# Sheet2.net
KiCad netlist of a schematic drawn in Altium Designer
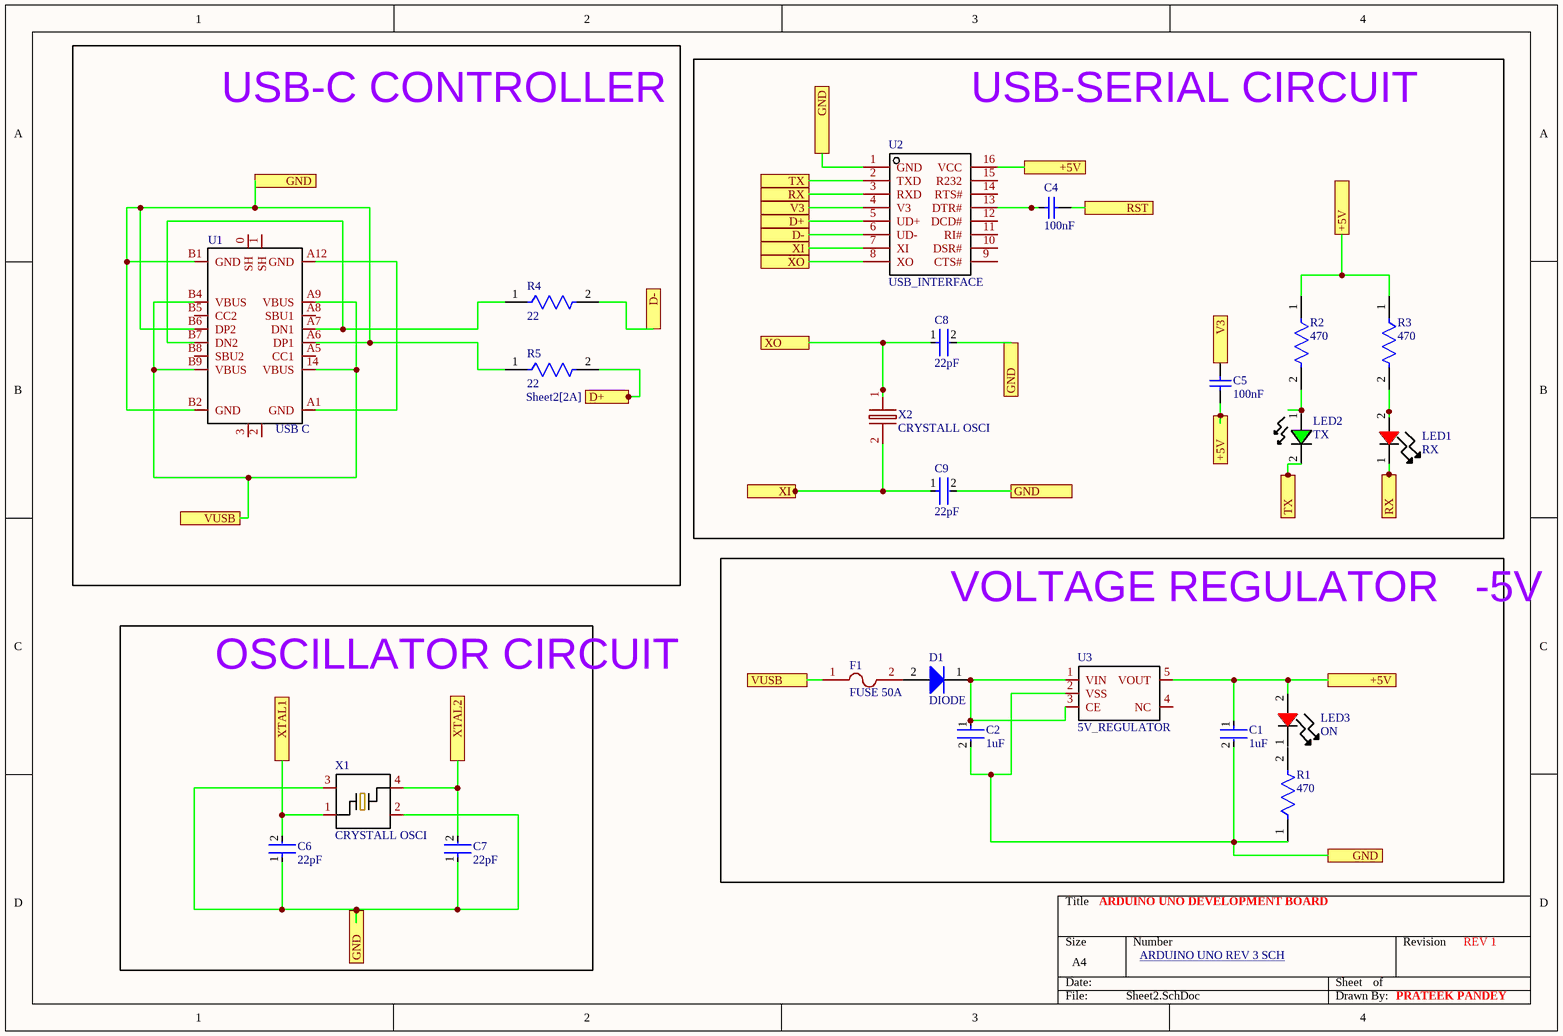
[diagram p0: Sheet2.SchDoc]

(export (version "E")
  (design (tool "Eeschema 10.0.6"))
  (components
    (comp (ref "C1")
      (value "1uF")
      (footprint "FP-0805-L_2_01_0_2-W_1_25-MFG")
      (description "General Purpose Ceramic Capacitor, 0805, 1uF, 10%, X7R, 15%, 25V")
      (fields (field (name "TOLERANCE") "10%") (field (name "VOLTAGE") "25V"))
      (libsource (lib "Altium Content Vault") (part "b4654b650e69147ec39a6b967a45e02"))
    )
    (comp (ref "C2")
      (value "1uF")
      (footprint "FP-0805-L_2_01_0_2-W_1_25-MFG")
      (description "General Purpose Ceramic Capacitor, 0805, 1uF, 10%, X7R, 15%, 25V")
      (fields (field (name "TOLERANCE") "10%") (field (name "VOLTAGE") "25V"))
      (libsource (lib "Altium Content Vault") (part "b4654b650e69147ec39a6b967a45e02"))
    )
    (comp (ref "C4")
      (value "100nF")
      (footprint "KEMT-1206-2_M")
      (description "CAP, Ceramic, 0.1 uF, +/- 10%, 50 V, -55 to 125 degC, 1206 (3216 Metric), RoHS, Tape and Reel")
      (fields (field (name "MANUFACTURER") "Kemet"))
      (libsource (lib "Altium Content Vault") (part "CAP-NP-2"))
    )
    (comp (ref "C5")
      (value "100nF")
      (footprint "KEMT-1206-2_M")
      (description "CAP, Ceramic, 0.1 uF, +/- 10%, 50 V, -55 to 125 degC, 1206 (3216 Metric), RoHS, Tape and Reel")
      (fields (field (name "MANUFACTURER") "Kemet"))
      (libsource (lib "Altium Content Vault") (part "CAP-NP-2"))
    )
    (comp (ref "C6")
      (value "22pF")
      (footprint "FP-C0805C-DN-MFG")
      (description "Capacitor; Ceramic; Cap; 22.0pF; Tol 5%; SMT; Vol-Rtg 50V; C0G; Tape and Reel")
      (fields
        (field (name "OCTOPART") "https://octopart.com/c0805c220j5gactu-kemet-145470")
        (field (name "MANUFACTURER") "KEMET")
      )
      (libsource (lib "Altium Content Vault") (part "b4654b650e69147ec39a6b967a45e02"))
    )
    (comp (ref "C7")
      (value "22pF")
      (footprint "FP-C0805C-DN-MFG")
      (description "Capacitor; Ceramic; Cap; 22.0pF; Tol 5%; SMT; Vol-Rtg 50V; C0G; Tape and Reel")
      (fields
        (field (name "OCTOPART") "https://octopart.com/c0805c220j5gactu-kemet-145470")
        (field (name "MANUFACTURER") "KEMET")
      )
      (libsource (lib "Altium Content Vault") (part "b4654b650e69147ec39a6b967a45e02"))
    )
    (comp (ref "C8")
      (value "22pF")
      (footprint "FP-C0805C-DN-MFG")
      (description "Capacitor; Ceramic; Cap; 22.0pF; Tol 5%; SMT; Vol-Rtg 50V; C0G; Tape and Reel")
      (fields
        (field (name "OCTOPART") "https://octopart.com/c0805c220j5gactu-kemet-145470")
        (field (name "MANUFACTURER") "KEMET")
      )
      (libsource (lib "Altium Content Vault") (part "b4654b650e69147ec39a6b967a45e02"))
    )
    (comp (ref "C9")
      (value "22pF")
      (footprint "FP-C0805C-DN-MFG")
      (description "Capacitor; Ceramic; Cap; 22.0pF; Tol 5%; SMT; Vol-Rtg 50V; C0G; Tape and Reel")
      (fields
        (field (name "OCTOPART") "https://octopart.com/c0805c220j5gactu-kemet-145470")
        (field (name "MANUFACTURER") "KEMET")
      )
      (libsource (lib "Altium Content Vault") (part "b4654b650e69147ec39a6b967a45e02"))
    )
    (comp (ref "D1")
      (value "DIODE")
      (footprint "ONSC-DSN-2-152AC-01_V")
      (description "Schottky Barrier Diode, 2-Pin DSN, Pb-Free, Tape and Reel")
      (fields (field (name "MANUFACTURER") "On Semiconductor") (field (name "PARTNUMBER") "NSR05F40NXT5G"))
      (libsource (lib "Altium Content Vault") (part "ONSC-D-K1A2-2"))
    )
    (comp (ref "F1")
      (value "FUSE 50A")
      (footprint "FUSE_50A:PCBComponent_1")
      (libsource (lib "FUSE_50A") (part "Component_1"))
    )
    (comp (ref "LED1")
      (value "RX")
      (footprint "LED_RED:LED_LSM0805-2P0X1P25X0P8_VCC")
      (libsource (lib "LED_RED") (part "Component_1"))
    )
    (comp (ref "LED2")
      (value "TX")
      (footprint "LED_GREEN:LED_05452V_VCC-M")
      (description "No Description Available")
      (libsource (lib "LED_GREEN") (part "LSM0805452V"))
    )
    (comp (ref "LED3")
      (value "ON")
      (footprint "LED_RED:LED_LSM0805-2P0X1P25X0P8_VCC")
      (libsource (lib "LED_RED") (part "Component_1"))
    )
    (comp (ref "R1")
      (value "470")
      (footprint "FP-CR0805-MFG")
      (description "Thick Film Chip Resistors 0805 470Ω 0.125W 5% 200ppm/°C")
      (fields (field (name "TOLERANCE") "5%"))
      (libsource (lib "Altium Content Vault") (part "1029c3af85768c4190bb7ad29bc67b5"))
    )
    (comp (ref "R2")
      (value "470")
      (footprint "FP-CR0805-MFG")
      (description "Thick Film Chip Resistors 0805 470Ω 0.125W 5% 200ppm/°C")
      (fields (field (name "TOLERANCE") "5%"))
      (libsource (lib "Altium Content Vault") (part "1029c3af85768c4190bb7ad29bc67b5"))
    )
    (comp (ref "R3")
      (value "470")
      (footprint "FP-CR0805-MFG")
      (description "Thick Film Chip Resistors 0805 470Ω 0.125W 5% 200ppm/°C")
      (fields (field (name "TOLERANCE") "5%"))
      (libsource (lib "Altium Content Vault") (part "1029c3af85768c4190bb7ad29bc67b5"))
    )
    (comp (ref "R4")
      (value "22")
      (footprint "FP-CR0603-IPC_A")
      (description "Thick Film Chip Resistors 0603 22Ω 0.1W 5% 200ppm/°C")
      (fields (field (name "TOLERANCE") "5%"))
      (libsource (lib "Altium Content Vault") (part "1029c3af85768c4190bb7ad29bc67b5"))
    )
    (comp (ref "R5")
      (value "22")
      (footprint "FP-CR0603-IPC_A")
      (description "Thick Film Chip Resistors 0603 22Ω 0.1W 5% 200ppm/°C")
      (fields (field (name "TOLERANCE") "5%"))
      (libsource (lib "Altium Content Vault") (part "1029c3af85768c4190bb7ad29bc67b5"))
    )
    (comp (ref "U1")
      (value "USB C")
      (footprint "USB-C_CONN:PCBComponent_1")
      (libsource (lib "USB-C_CONN") (part "Component_1"))
    )
    (comp (ref "U2")
      (value "USB_INTERFACE")
      (footprint "USB_INTERFACE:PCBComponent_1")
      (libsource (lib "USB_INTERFACE") (part "Component_1"))
    )
    (comp (ref "U3")
      (value "5V_REGULATOR")
      (footprint "5V_REG:PCBComponent_1")
      (libsource (lib "Schlib1'") (part "Component_1"))
    )
    (comp (ref "X1")
      (value "CRYSTALL OSCI")
      (footprint "PCBComponent_1")
      (libsource (lib "Schlib1") (part "Component_1"))
    )
    (comp (ref "X2")
      (value "CRYSTALL OSCI")
      (footprint "OSCILL_12MHz:PCBComponent_1")
      (libsource (lib "OSCILL_12MHz") (part "Component_1"))
    )
  )
  (nets
    (net (code "1") (name "/+5V") (class "Default")
      (node (ref "C1") (pin "1") (pinfunction "1_1") (pintype "passive"))
      (node (ref "C5") (pin "2") (pinfunction "2_2") (pintype "passive"))
      (node (ref "LED3") (pin "2") (pinfunction "+_2") (pintype "passive"))
      (node (ref "R2") (pin "1") (pinfunction "1_1") (pintype "passive"))
      (node (ref "R3") (pin "1") (pinfunction "1_1") (pintype "passive"))
      (node (ref "U2") (pin "16") (pinfunction "VCC_16") (pintype "passive"))
      (node (ref "U3") (pin "5") (pinfunction "VOUT_5") (pintype "passive"))
    )
    (net (code "2") (name "/D+") (class "Default")
      (node (ref "R5") (pin "2") (pinfunction "2_2") (pintype "passive"))
      (node (ref "U2") (pin "5") (pinfunction "UD+_5") (pintype "passive"))
    )
    (net (code "3") (name "/D-") (class "Default")
      (node (ref "R4") (pin "2") (pinfunction "2_2") (pintype "passive"))
      (node (ref "U2") (pin "6") (pinfunction "UD-_6") (pintype "passive"))
    )
    (net (code "4") (name "/GND") (class "Default")
      (node (ref "C1") (pin "2") (pinfunction "2_2") (pintype "passive"))
      (node (ref "C2") (pin "2") (pinfunction "2_2") (pintype "passive"))
      (node (ref "C6") (pin "1") (pinfunction "1_1") (pintype "passive"))
      (node (ref "C7") (pin "1") (pinfunction "1_1") (pintype "passive"))
      (node (ref "C8") (pin "2") (pinfunction "2_2") (pintype "passive"))
      (node (ref "C9") (pin "2") (pinfunction "2_2") (pintype "passive"))
      (node (ref "R1") (pin "1") (pinfunction "1_1") (pintype "passive"))
      (node (ref "R5") (pin "1") (pinfunction "1_1") (pintype "passive"))
      (node (ref "U1") (pin "A6") (pinfunction "DP1_A6") (pintype "passive"))
      (node (ref "U1") (pin "B1") (pinfunction "GND_B1") (pintype "passive"))
      (node (ref "U1") (pin "B2") (pinfunction "GND_B2") (pintype "passive"))
      (node (ref "U1") (pin "B6") (pinfunction "DP2_B6") (pintype "passive"))
      (node (ref "U2") (pin "1") (pinfunction "GND_1") (pintype "passive"))
      (node (ref "U3") (pin "2") (pinfunction "VSS_2") (pintype "passive"))
      (node (ref "X1") (pin "2") (pinfunction "2_2") (pintype "passive"))
      (node (ref "X1") (pin "3") (pinfunction "3_3") (pintype "passive"))
    )
    (net (code "5") (name "/RST") (class "Default")
      (node (ref "C4") (pin "1") (pinfunction "1_1") (pintype "passive"))
    )
    (net (code "6") (name "/RX") (class "Default")
      (node (ref "LED1") (pin "1") (pinfunction "-_1") (pintype "passive"))
      (node (ref "U2") (pin "3") (pinfunction "RXD_3") (pintype "passive"))
    )
    (net (code "7") (name "/TX") (class "Default")
      (node (ref "LED2") (pin "2") (pinfunction "2_2") (pintype "passive"))
      (node (ref "U2") (pin "2") (pinfunction "TXD_2") (pintype "passive"))
    )
    (net (code "8") (name "/V3") (class "Default")
      (node (ref "C5") (pin "1") (pinfunction "1_1") (pintype "passive"))
      (node (ref "U2") (pin "4") (pinfunction "V3_4") (pintype "passive"))
    )
    (net (code "9") (name "/VUSB") (class "Default")
      (node (ref "F1") (pin "1") (pinfunction "1_1") (pintype "passive"))
      (node (ref "U1") (pin "14") (pinfunction "VBUS_14") (pintype "passive"))
      (node (ref "U1") (pin "A9") (pinfunction "VBUS_A9") (pintype "passive"))
      (node (ref "U1") (pin "B4") (pinfunction "VBUS_B4") (pintype "passive"))
      (node (ref "U1") (pin "B9") (pinfunction "VBUS_B9") (pintype "passive"))
    )
    (net (code "10") (name "/XI") (class "Default")
      (node (ref "C9") (pin "1") (pinfunction "1_1") (pintype "passive"))
      (node (ref "U2") (pin "7") (pinfunction "XI_7") (pintype "passive"))
      (node (ref "X2") (pin "2") (pinfunction "2_2") (pintype "passive"))
    )
    (net (code "11") (name "/XO") (class "Default")
      (node (ref "C8") (pin "1") (pinfunction "1_1") (pintype "passive"))
      (node (ref "U2") (pin "8") (pinfunction "XO_8") (pintype "passive"))
      (node (ref "X2") (pin "1") (pinfunction "1_1") (pintype "passive"))
    )
    (net (code "12") (name "/XTAL1") (class "Default")
      (node (ref "C6") (pin "2") (pinfunction "2_2") (pintype "passive"))
      (node (ref "X1") (pin "1") (pinfunction "1_1") (pintype "passive"))
    )
    (net (code "13") (name "/XTAL2") (class "Default")
      (node (ref "C7") (pin "2") (pinfunction "2_2") (pintype "passive"))
      (node (ref "X1") (pin "4") (pinfunction "4_4") (pintype "passive"))
    )
    (net (code "14") (name "Net-(D1-A)") (class "Default")
      (node (ref "D1") (pin "2") (pinfunction "A_2") (pintype "passive"))
      (node (ref "F1") (pin "2") (pinfunction "2_2") (pintype "passive"))
    )
    (net (code "15") (name "Net-(D1-K)") (class "Default")
      (node (ref "C2") (pin "1") (pinfunction "1_1") (pintype "passive"))
      (node (ref "D1") (pin "1") (pinfunction "K_1") (pintype "passive"))
      (node (ref "U3") (pin "1") (pinfunction "VIN_1") (pintype "passive"))
      (node (ref "U3") (pin "3") (pinfunction "CE_3") (pintype "passive"))
    )
    (net (code "16") (name "Net-(LED1-+)") (class "Default")
      (node (ref "LED1") (pin "2") (pinfunction "+_2") (pintype "passive"))
      (node (ref "R3") (pin "2") (pinfunction "2_2") (pintype "passive"))
    )
    (net (code "17") (name "Net-(LED2-Pad1)") (class "Default")
      (node (ref "LED2") (pin "1") (pinfunction "1_1") (pintype "passive"))
      (node (ref "R2") (pin "2") (pinfunction "2_2") (pintype "passive"))
    )
    (net (code "18") (name "Net-(U1-DN1)") (class "Default")
      (node (ref "R4") (pin "1") (pinfunction "1_1") (pintype "passive"))
      (node (ref "U1") (pin "A7") (pinfunction "DN1_A7") (pintype "passive"))
      (node (ref "U1") (pin "B7") (pinfunction "DN2_B7") (pintype "passive"))
    )
    (net (code "19") (name "Net-(U1-GND-PadA1)") (class "Default")
      (node (ref "U1") (pin "A1") (pinfunction "GND_A1") (pintype "passive"))
      (node (ref "U1") (pin "A12") (pinfunction "GND_A12") (pintype "passive"))
    )
    (net (code "20") (name "Net-(U2-DTR#)") (class "Default")
      (node (ref "C4") (pin "2") (pinfunction "2_2") (pintype "passive"))
      (node (ref "U2") (pin "13") (pinfunction "DTR#_13") (pintype "passive"))
    )
    (net (code "21") (name "unconnected-(LED3---Pad1)") (class "Default")
      (node (ref "LED3") (pin "1") (pinfunction "-_1") (pintype "passive"))
    )
    (net (code "22") (name "unconnected-(R1-Pad2)") (class "Default")
      (node (ref "R1") (pin "2") (pinfunction "2_2") (pintype "passive"))
    )
    (net (code "23") (name "unconnected-(U1-CC1-PadA5)") (class "Default")
      (node (ref "U1") (pin "A5") (pinfunction "CC1_A5") (pintype "passive"))
    )
    (net (code "24") (name "unconnected-(U1-CC2-PadB5)") (class "Default")
      (node (ref "U1") (pin "B5") (pinfunction "CC2_B5") (pintype "passive"))
    )
    (net (code "25") (name "unconnected-(U1-Pad2)") (class "Default")
      (node (ref "U1") (pin "2") (pinfunction "2_2") (pintype "passive"))
    )
    (net (code "26") (name "unconnected-(U1-Pad3)") (class "Default")
      (node (ref "U1") (pin "3") (pinfunction "3_3") (pintype "passive"))
    )
    (net (code "27") (name "unconnected-(U1-SBU1-PadA8)") (class "Default")
      (node (ref "U1") (pin "A8") (pinfunction "SBU1_A8") (pintype "passive"))
    )
    (net (code "28") (name "unconnected-(U1-SBU2-PadB8)") (class "Default")
      (node (ref "U1") (pin "B8") (pinfunction "SBU2_B8") (pintype "passive"))
    )
    (net (code "29") (name "unconnected-(U1-SH-Pad0)") (class "Default")
      (node (ref "U1") (pin "0") (pinfunction "SH_0") (pintype "passive"))
    )
    (net (code "30") (name "unconnected-(U1-SH-Pad1)") (class "Default")
      (node (ref "U1") (pin "1") (pinfunction "SH_1") (pintype "passive"))
    )
    (net (code "31") (name "unconnected-(U2-CTS#-Pad9)") (class "Default")
      (node (ref "U2") (pin "9") (pinfunction "CTS#_9") (pintype "passive"))
    )
    (net (code "32") (name "unconnected-(U2-DCD#-Pad12)") (class "Default")
      (node (ref "U2") (pin "12") (pinfunction "DCD#_12") (pintype "passive"))
    )
    (net (code "33") (name "unconnected-(U2-DSR#-Pad10)") (class "Default")
      (node (ref "U2") (pin "10") (pinfunction "DSR#_10") (pintype "passive"))
    )
    (net (code "34") (name "unconnected-(U2-R232-Pad15)") (class "Default")
      (node (ref "U2") (pin "15") (pinfunction "R232_15") (pintype "passive"))
    )
    (net (code "35") (name "unconnected-(U2-RI#-Pad11)") (class "Default")
      (node (ref "U2") (pin "11") (pinfunction "RI#_11") (pintype "passive"))
    )
    (net (code "36") (name "unconnected-(U2-RTS#-Pad14)") (class "Default")
      (node (ref "U2") (pin "14") (pinfunction "RTS#_14") (pintype "passive"))
    )
    (net (code "37") (name "unconnected-(U3-NC-Pad4)") (class "Default")
      (node (ref "U3") (pin "4") (pinfunction "NC_4") (pintype "passive"))
    )
  )
)
